# design.net
KiCad netlist of a schematic drawn in Altium Designer
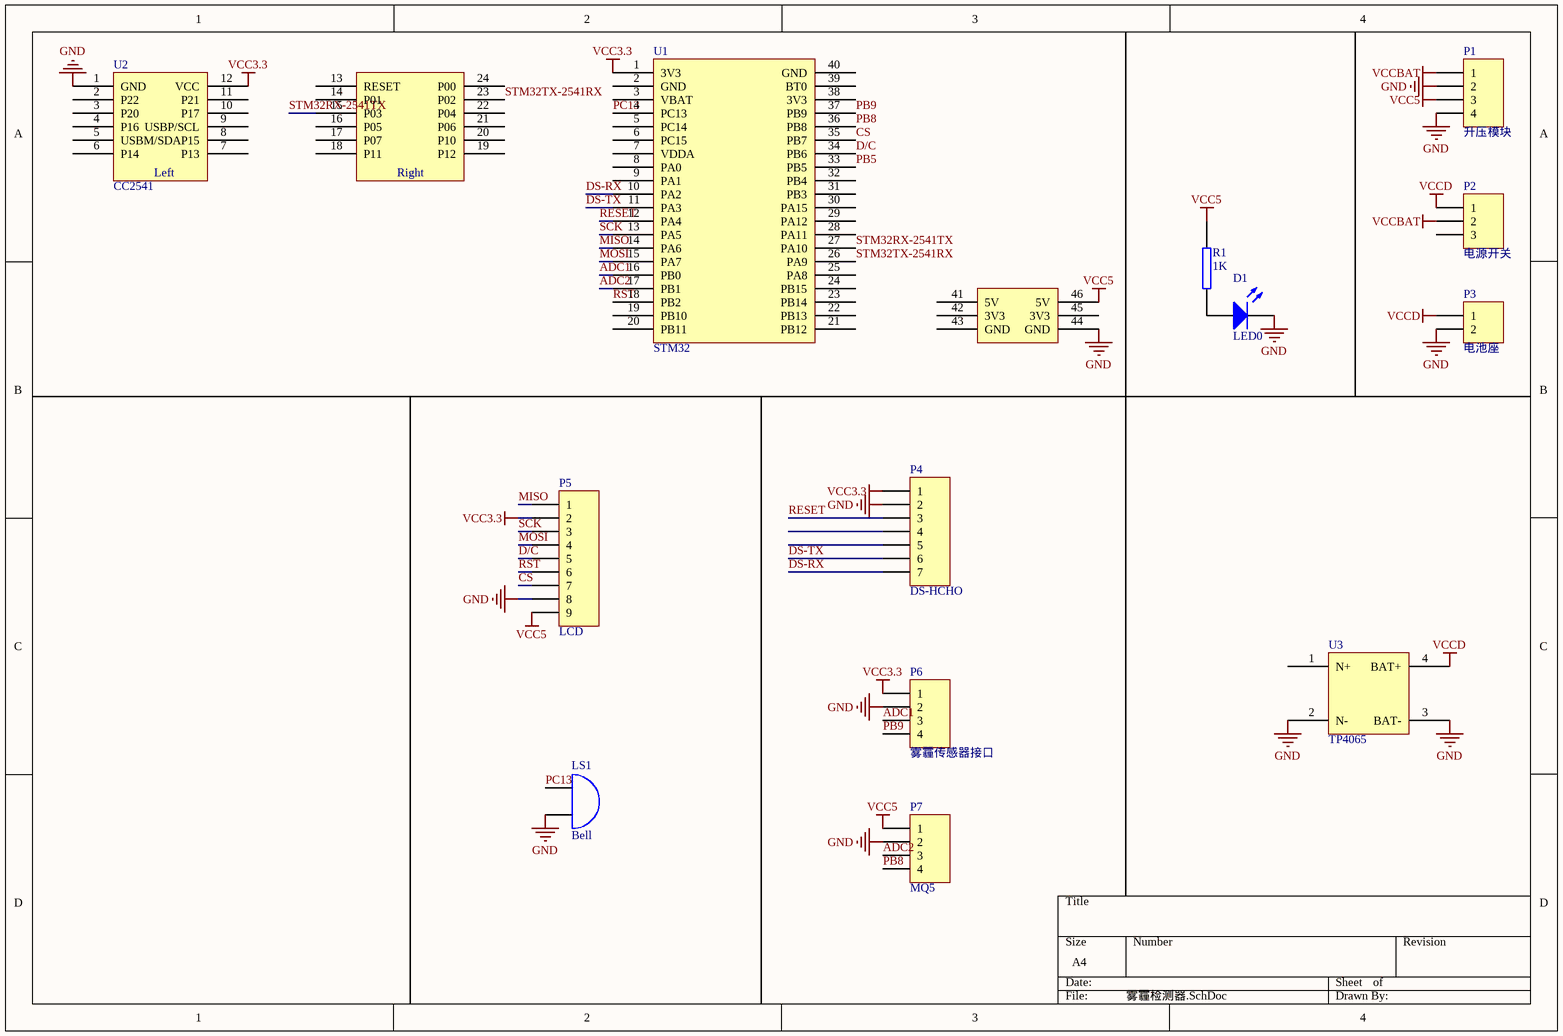
[diagram p0: 雾霾检测器.SchDoc]

(export (version "E")
  (design (tool "Eeschema 10.0.6"))
  (components
    (comp (ref "D1")
      (value "LED0")
      (footprint "0805-led")
      (description "Typical INFRARED GaAs LED")
      (fields (field (name "PUBLISHER") "Altium Limited"))
      (libsource (lib "Miscellaneous Devices") (part "LED0"))
    )
    (comp (ref "LS1")
      (value "Bell")
      (footprint "BUZZER-12MM")
      (description "Electrical Bell")
      (fields (field (name "PUBLISHER") "Altium Limited"))
      (libsource (lib "Miscellaneous Devices") (part "Bell"))
    )
    (comp (ref "P1")
      (value "升压模块")
      (footprint "DC-DC升压模块")
      (description "Header, 4-Pin")
      (fields (field (name "PUBLISHER") "Altium Limited"))
      (libsource (lib "Miscellaneous Connectors") (part "Header 4"))
    )
    (comp (ref "P2")
      (value "电源开关")
      (footprint "拨动开关（2mm）")
      (description "Header, 3-Pin")
      (fields (field (name "PUBLISHER") "Altium Limited"))
      (libsource (lib "Miscellaneous Connectors") (part "Header 3"))
    )
    (comp (ref "P3")
      (value "电池座")
      (footprint "7号电池盒-4.5CM")
      (description "Header, 2-Pin")
      (fields (field (name "PUBLISHER") "Altium Limited"))
      (libsource (lib "Miscellaneous Connectors") (part "Header 2"))
    )
    (comp (ref "P4")
      (value "DS-HCHO")
      (footprint "HDR1X7")
      (description "Header, 7-Pin")
      (fields (field (name "PUBLISHER") "Altium Limited"))
      (libsource (lib "Miscellaneous Connectors") (part "Header 7"))
    )
    (comp (ref "P5")
      (value "LCD")
      (footprint "HDR1X9")
      (description "Header, 9-Pin")
      (fields (field (name "PUBLISHER") "Altium Limited"))
      (libsource (lib "Miscellaneous Connectors") (part "Header 9"))
    )
    (comp (ref "P6")
      (value "雾霾传感器接口")
      (footprint "HDR1X4")
      (description "Header, 4-Pin")
      (fields (field (name "PUBLISHER") "Altium Limited"))
      (libsource (lib "Miscellaneous Connectors") (part "Header 4"))
    )
    (comp (ref "P7")
      (value "MQ5")
      (footprint "HDR1X4")
      (description "Header, 4-Pin")
      (fields (field (name "PUBLISHER") "Altium Limited"))
      (libsource (lib "Miscellaneous Connectors") (part "Header 4"))
    )
    (comp (ref "R1") (value "1K") (footprint "0805-SMALL") (libsource (lib "CC254xEM原理图库") (part "RES2")))
    (comp (ref "U1") (value "STM32") (footprint "STM32_Smart") (libsource (lib "我的原理图") (part "STM32_Smart")))
    (comp (ref "U2")
      (value "CC2541")
      (footprint "Smart_RF_2541")
      (libsource (lib "我的原理图") (part "Smart_RF_2541"))
    )
    (comp (ref "U3") (value "TP4065") (footprint "TP4065_模块") (libsource (lib "我的原理图") (part "TP4056_ 模块")))
  )
  (nets
    (net (code "1") (name "/ADC1") (class "Default")
      (node (ref "P6") (pin "3") (pinfunction "3_3") (pintype "passive"))
      (node (ref "U1") (pin "16") (pinfunction "PB0_16") (pintype "passive"))
    )
    (net (code "2") (name "/ADC2") (class "Default")
      (node (ref "P7") (pin "3") (pinfunction "3_3") (pintype "passive"))
      (node (ref "U1") (pin "17") (pinfunction "PB1_17") (pintype "passive"))
    )
    (net (code "3") (name "/CS") (class "Default")
      (node (ref "P5") (pin "7") (pinfunction "7_7") (pintype "passive"))
      (node (ref "U1") (pin "35") (pinfunction "PB7_35") (pintype "passive"))
    )
    (net (code "4") (name "/DS-RX") (class "Default")
      (node (ref "P4") (pin "7") (pinfunction "7_7") (pintype "passive"))
      (node (ref "U1") (pin "10") (pinfunction "PA2_10") (pintype "passive"))
    )
    (net (code "5") (name "/DS-TX") (class "Default")
      (node (ref "P4") (pin "6") (pinfunction "6_6") (pintype "passive"))
      (node (ref "U1") (pin "11") (pinfunction "PA3_11") (pintype "passive"))
    )
    (net (code "6") (name "/D{slash}C") (class "Default")
      (node (ref "P5") (pin "5") (pinfunction "5_5") (pintype "passive"))
      (node (ref "U1") (pin "34") (pinfunction "PB6_34") (pintype "passive"))
    )
    (net (code "7") (name "/MISO") (class "Default")
      (node (ref "P5") (pin "1") (pinfunction "1_1") (pintype "passive"))
      (node (ref "U1") (pin "14") (pinfunction "PA6_14") (pintype "passive"))
    )
    (net (code "8") (name "/MOSI") (class "Default")
      (node (ref "P5") (pin "4") (pinfunction "4_4") (pintype "passive"))
      (node (ref "U1") (pin "15") (pinfunction "PA7_15") (pintype "passive"))
    )
    (net (code "9") (name "/PB5") (class "Default")
      (node (ref "U1") (pin "33") (pinfunction "PB5_33") (pintype "passive"))
    )
    (net (code "10") (name "/PB8") (class "Default")
      (node (ref "P7") (pin "4") (pinfunction "4_4") (pintype "passive"))
      (node (ref "U1") (pin "36") (pinfunction "PB8_36") (pintype "passive"))
    )
    (net (code "11") (name "/PB9") (class "Default")
      (node (ref "P6") (pin "4") (pinfunction "4_4") (pintype "passive"))
      (node (ref "U1") (pin "37") (pinfunction "PB9_37") (pintype "passive"))
    )
    (net (code "12") (name "/PC13") (class "Default")
      (node (ref "LS1") (pin "1") (pinfunction "A_1") (pintype "passive"))
      (node (ref "U1") (pin "4") (pinfunction "PC13_4") (pintype "passive"))
    )
    (net (code "13") (name "/RESET") (class "Default")
      (node (ref "P4") (pin "3") (pinfunction "3_3") (pintype "passive"))
      (node (ref "U1") (pin "12") (pinfunction "PA4_12") (pintype "passive"))
    )
    (net (code "14") (name "/RST") (class "Default")
      (node (ref "P5") (pin "6") (pinfunction "6_6") (pintype "passive"))
      (node (ref "U1") (pin "18") (pinfunction "PB2_18") (pintype "passive"))
    )
    (net (code "15") (name "/SCK") (class "Default")
      (node (ref "P5") (pin "3") (pinfunction "3_3") (pintype "passive"))
      (node (ref "U1") (pin "13") (pinfunction "PA5_13") (pintype "passive"))
    )
    (net (code "16") (name "/STM32RX-2541TX") (class "Default")
      (node (ref "U1") (pin "27") (pinfunction "PA10_27") (pintype "passive"))
      (node (ref "U2") (pin "15") (pinfunction "P03_15") (pintype "passive"))
    )
    (net (code "17") (name "/STM32TX-2541RX") (class "Default")
      (node (ref "U1") (pin "26") (pinfunction "PA9_26") (pintype "passive"))
      (node (ref "U2") (pin "23") (pinfunction "P02_23") (pintype "passive"))
    )
    (net (code "18") (name "GND") (class "Default")
      (node (ref "D1") (pin "2") (pinfunction "K_2") (pintype "passive"))
      (node (ref "LS1") (pin "2") (pinfunction "B_2") (pintype "passive"))
      (node (ref "P1") (pin "2") (pinfunction "2_2") (pintype "passive"))
      (node (ref "P1") (pin "4") (pinfunction "4_4") (pintype "passive"))
      (node (ref "P3") (pin "2") (pinfunction "2_2") (pintype "passive"))
      (node (ref "P4") (pin "2") (pinfunction "2_2") (pintype "passive"))
      (node (ref "P5") (pin "8") (pinfunction "8_8") (pintype "passive"))
      (node (ref "P6") (pin "2") (pinfunction "2_2") (pintype "passive"))
      (node (ref "P7") (pin "2") (pinfunction "2_2") (pintype "passive"))
      (node (ref "U1") (pin "44") (pinfunction "GND_44") (pintype "passive"))
      (node (ref "U2") (pin "1") (pinfunction "GND_1") (pintype "passive"))
      (node (ref "U3") (pin "2") (pinfunction "N-_2") (pintype "passive"))
      (node (ref "U3") (pin "3") (pinfunction "BAT-_3") (pintype "passive"))
    )
    (net (code "19") (name "Net-(D1-A)") (class "Default")
      (node (ref "D1") (pin "1") (pinfunction "A_1") (pintype "passive"))
      (node (ref "R1") (pin "1") (pinfunction "1_1") (pintype "passive"))
    )
    (net (code "20") (name "VCC3.3") (class "Default")
      (node (ref "P4") (pin "1") (pinfunction "1_1") (pintype "passive"))
      (node (ref "P5") (pin "2") (pinfunction "2_2") (pintype "passive"))
      (node (ref "P6") (pin "1") (pinfunction "1_1") (pintype "passive"))
      (node (ref "U1") (pin "1") (pinfunction "3V3_1") (pintype "passive"))
      (node (ref "U2") (pin "12") (pinfunction "VCC_12") (pintype "passive"))
    )
    (net (code "21") (name "VCC5") (class "Default")
      (node (ref "P1") (pin "3") (pinfunction "3_3") (pintype "passive"))
      (node (ref "P5") (pin "9") (pinfunction "9_9") (pintype "passive"))
      (node (ref "P7") (pin "1") (pinfunction "1_1") (pintype "passive"))
      (node (ref "R1") (pin "2") (pinfunction "2_2") (pintype "passive"))
      (node (ref "U1") (pin "46") (pinfunction "5V_46") (pintype "passive"))
    )
    (net (code "22") (name "VCCBAT") (class "Default")
      (node (ref "P1") (pin "1") (pinfunction "1_1") (pintype "passive"))
      (node (ref "P2") (pin "2") (pinfunction "2_2") (pintype "passive"))
    )
    (net (code "23") (name "VCCD") (class "Default")
      (node (ref "P2") (pin "1") (pinfunction "1_1") (pintype "passive"))
      (node (ref "P3") (pin "1") (pinfunction "1_1") (pintype "passive"))
      (node (ref "U3") (pin "4") (pinfunction "BAT+_4") (pintype "passive"))
    )
    (net (code "24") (name "unconnected-(P2-Pad3)") (class "Default")
      (node (ref "P2") (pin "3") (pinfunction "3_3") (pintype "passive"))
    )
    (net (code "25") (name "unconnected-(P4-Pad4)") (class "Default")
      (node (ref "P4") (pin "4") (pinfunction "4_4") (pintype "passive"))
    )
    (net (code "26") (name "unconnected-(P4-Pad5)") (class "Default")
      (node (ref "P4") (pin "5") (pinfunction "5_5") (pintype "passive"))
    )
    (net (code "27") (name "unconnected-(U1-3V3-Pad38)") (class "Default")
      (node (ref "U1") (pin "38") (pinfunction "3V3_38") (pintype "passive"))
    )
    (net (code "28") (name "unconnected-(U1-3V3-Pad42)") (class "Default")
      (node (ref "U1") (pin "42") (pinfunction "3V3_42") (pintype "passive"))
    )
    (net (code "29") (name "unconnected-(U1-3V3-Pad45)") (class "Default")
      (node (ref "U1") (pin "45") (pinfunction "3V3_45") (pintype "passive"))
    )
    (net (code "30") (name "unconnected-(U1-5V-Pad41)") (class "Default")
      (node (ref "U1") (pin "41") (pinfunction "5V_41") (pintype "passive"))
    )
    (net (code "31") (name "unconnected-(U1-BT0-Pad39)") (class "Default")
      (node (ref "U1") (pin "39") (pinfunction "BT0_39") (pintype "passive"))
    )
    (net (code "32") (name "unconnected-(U1-GND-Pad2)") (class "Default")
      (node (ref "U1") (pin "2") (pinfunction "GND_2") (pintype "passive"))
    )
    (net (code "33") (name "unconnected-(U1-GND-Pad40)") (class "Default")
      (node (ref "U1") (pin "40") (pinfunction "GND_40") (pintype "passive"))
    )
    (net (code "34") (name "unconnected-(U1-GND-Pad43)") (class "Default")
      (node (ref "U1") (pin "43") (pinfunction "GND_43") (pintype "passive"))
    )
    (net (code "35") (name "unconnected-(U1-PA0-Pad8)") (class "Default")
      (node (ref "U1") (pin "8") (pinfunction "PA0_8") (pintype "passive"))
    )
    (net (code "36") (name "unconnected-(U1-PA1-Pad9)") (class "Default")
      (node (ref "U1") (pin "9") (pinfunction "PA1_9") (pintype "passive"))
    )
    (net (code "37") (name "unconnected-(U1-PA8-Pad25)") (class "Default")
      (node (ref "U1") (pin "25") (pinfunction "PA8_25") (pintype "passive"))
    )
    (net (code "38") (name "unconnected-(U1-PA11-Pad28)") (class "Default")
      (node (ref "U1") (pin "28") (pinfunction "PA11_28") (pintype "passive"))
    )
    (net (code "39") (name "unconnected-(U1-PA12-Pad29)") (class "Default")
      (node (ref "U1") (pin "29") (pinfunction "PA12_29") (pintype "passive"))
    )
    (net (code "40") (name "unconnected-(U1-PA15-Pad30)") (class "Default")
      (node (ref "U1") (pin "30") (pinfunction "PA15_30") (pintype "passive"))
    )
    (net (code "41") (name "unconnected-(U1-PB3-Pad31)") (class "Default")
      (node (ref "U1") (pin "31") (pinfunction "PB3_31") (pintype "passive"))
    )
    (net (code "42") (name "unconnected-(U1-PB4-Pad32)") (class "Default")
      (node (ref "U1") (pin "32") (pinfunction "PB4_32") (pintype "passive"))
    )
    (net (code "43") (name "unconnected-(U1-PB10-Pad19)") (class "Default")
      (node (ref "U1") (pin "19") (pinfunction "PB10_19") (pintype "passive"))
    )
    (net (code "44") (name "unconnected-(U1-PB11-Pad20)") (class "Default")
      (node (ref "U1") (pin "20") (pinfunction "PB11_20") (pintype "passive"))
    )
    (net (code "45") (name "unconnected-(U1-PB12-Pad21)") (class "Default")
      (node (ref "U1") (pin "21") (pinfunction "PB12_21") (pintype "passive"))
    )
    (net (code "46") (name "unconnected-(U1-PB13-Pad22)") (class "Default")
      (node (ref "U1") (pin "22") (pinfunction "PB13_22") (pintype "passive"))
    )
    (net (code "47") (name "unconnected-(U1-PB14-Pad23)") (class "Default")
      (node (ref "U1") (pin "23") (pinfunction "PB14_23") (pintype "passive"))
    )
    (net (code "48") (name "unconnected-(U1-PB15-Pad24)") (class "Default")
      (node (ref "U1") (pin "24") (pinfunction "PB15_24") (pintype "passive"))
    )
    (net (code "49") (name "unconnected-(U1-PC14-Pad5)") (class "Default")
      (node (ref "U1") (pin "5") (pinfunction "PC14_5") (pintype "passive"))
    )
    (net (code "50") (name "unconnected-(U1-PC15-Pad6)") (class "Default")
      (node (ref "U1") (pin "6") (pinfunction "PC15_6") (pintype "passive"))
    )
    (net (code "51") (name "unconnected-(U1-VBAT-Pad3)") (class "Default")
      (node (ref "U1") (pin "3") (pinfunction "VBAT_3") (pintype "passive"))
    )
    (net (code "52") (name "unconnected-(U1-VDDA-Pad7)") (class "Default")
      (node (ref "U1") (pin "7") (pinfunction "VDDA_7") (pintype "passive"))
    )
    (net (code "53") (name "unconnected-(U2-P00-Pad24)") (class "Default")
      (node (ref "U2") (pin "24") (pinfunction "P00_24") (pintype "passive"))
    )
    (net (code "54") (name "unconnected-(U2-P01-Pad14)") (class "Default")
      (node (ref "U2") (pin "14") (pinfunction "P01_14") (pintype "passive"))
    )
    (net (code "55") (name "unconnected-(U2-P04-Pad22)") (class "Default")
      (node (ref "U2") (pin "22") (pinfunction "P04_22") (pintype "passive"))
    )
    (net (code "56") (name "unconnected-(U2-P05-Pad16)") (class "Default")
      (node (ref "U2") (pin "16") (pinfunction "P05_16") (pintype "passive"))
    )
    (net (code "57") (name "unconnected-(U2-P06-Pad21)") (class "Default")
      (node (ref "U2") (pin "21") (pinfunction "P06_21") (pintype "passive"))
    )
    (net (code "58") (name "unconnected-(U2-P07-Pad17)") (class "Default")
      (node (ref "U2") (pin "17") (pinfunction "P07_17") (pintype "passive"))
    )
    (net (code "59") (name "unconnected-(U2-P10-Pad20)") (class "Default")
      (node (ref "U2") (pin "20") (pinfunction "P10_20") (pintype "passive"))
    )
    (net (code "60") (name "unconnected-(U2-P11-Pad18)") (class "Default")
      (node (ref "U2") (pin "18") (pinfunction "P11_18") (pintype "passive"))
    )
    (net (code "61") (name "unconnected-(U2-P12-Pad19)") (class "Default")
      (node (ref "U2") (pin "19") (pinfunction "P12_19") (pintype "passive"))
    )
    (net (code "62") (name "unconnected-(U2-P13-Pad7)") (class "Default")
      (node (ref "U2") (pin "7") (pinfunction "P13_7") (pintype "passive"))
    )
    (net (code "63") (name "unconnected-(U2-P14-Pad6)") (class "Default")
      (node (ref "U2") (pin "6") (pinfunction "P14_6") (pintype "passive"))
    )
    (net (code "64") (name "unconnected-(U2-P15-Pad8)") (class "Default")
      (node (ref "U2") (pin "8") (pinfunction "P15_8") (pintype "passive"))
    )
    (net (code "65") (name "unconnected-(U2-P16-Pad4)") (class "Default")
      (node (ref "U2") (pin "4") (pinfunction "P16_4") (pintype "passive"))
    )
    (net (code "66") (name "unconnected-(U2-P17-Pad10)") (class "Default")
      (node (ref "U2") (pin "10") (pinfunction "P17_10") (pintype "passive"))
    )
    (net (code "67") (name "unconnected-(U2-P20-Pad3)") (class "Default")
      (node (ref "U2") (pin "3") (pinfunction "P20_3") (pintype "passive"))
    )
    (net (code "68") (name "unconnected-(U2-P21-Pad11)") (class "Default")
      (node (ref "U2") (pin "11") (pinfunction "P21_11") (pintype "passive"))
    )
    (net (code "69") (name "unconnected-(U2-P22-Pad2)") (class "Default")
      (node (ref "U2") (pin "2") (pinfunction "P22_2") (pintype "passive"))
    )
    (net (code "70") (name "unconnected-(U2-RESET-Pad13)") (class "Default")
      (node (ref "U2") (pin "13") (pinfunction "RESET_13") (pintype "passive"))
    )
    (net (code "71") (name "unconnected-(U2-USBM{slash}SDA-Pad5)") (class "Default")
      (node (ref "U2") (pin "5") (pinfunction "USBM/SDA_5") (pintype "passive"))
    )
    (net (code "72") (name "unconnected-(U2-USBP{slash}SCL-Pad9)") (class "Default")
      (node (ref "U2") (pin "9") (pinfunction "USBP/SCL_9") (pintype "passive"))
    )
    (net (code "73") (name "unconnected-(U3-N+-Pad1)") (class "Default")
      (node (ref "U3") (pin "1") (pinfunction "N+_1") (pintype "passive"))
    )
  )
)
